# Motherboard.net
KiCad netlist of a schematic drawn in EAGLE
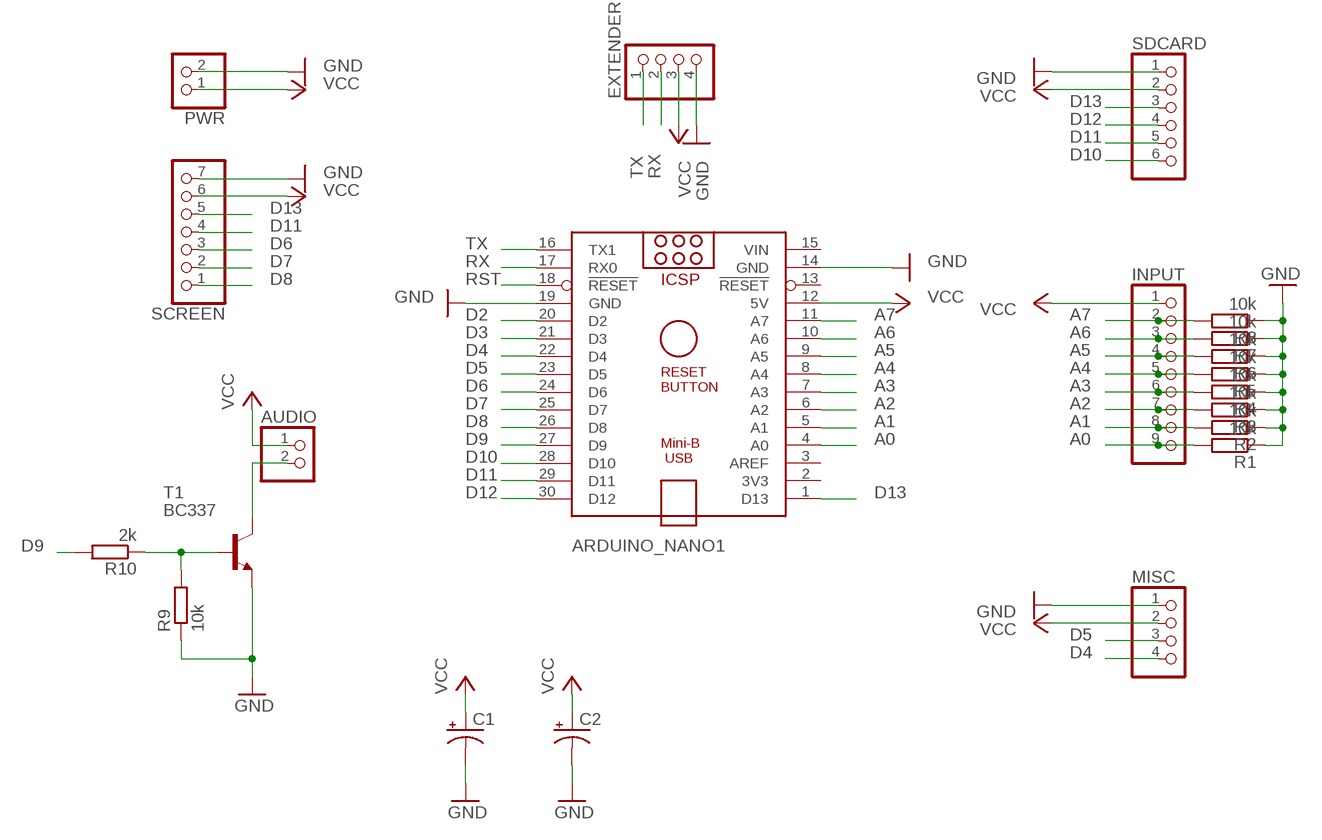
[diagram p0: schematic, sheet 1]

(export (version "E")
  (design (tool "Eeschema 10.0.6"))
  (components
    (comp (ref "ARDUINO_NANO1")
      (value "ARDUINO_NANO")
      (footprint "eagle-import:ARDUINO_NANO")
      (libsource (lib "eagle-import") (part "ARDUINO_NANO"))
    )
    (comp (ref "AUDIO")
      (value "PINHD-1X2")
      (footprint "eagle-import:1X02")
      (libsource (lib "eagle-import") (part "PINHD-1X2"))
    )
    (comp (ref "C1")
      (value "CPOL-USE2.5-6")
      (footprint "eagle-import:E2,5-6")
      (libsource (lib "eagle-import") (part "CPOL-USE2.5-6"))
    )
    (comp (ref "C2")
      (value "CPOL-USE2.5-6")
      (footprint "eagle-import:E2,5-6")
      (libsource (lib "eagle-import") (part "CPOL-USE2.5-6"))
    )
    (comp (ref "EXTENDER")
      (value "PINHD-1X4")
      (footprint "eagle-import:1X04")
      (libsource (lib "eagle-import") (part "PINHD-1X4"))
    )
    (comp (ref "INPUT")
      (value "PINHD-1X9")
      (footprint "eagle-import:1X09")
      (libsource (lib "eagle-import") (part "PINHD-1X9"))
    )
    (comp (ref "MISC")
      (value "PINHD-1X4")
      (footprint "eagle-import:1X04")
      (libsource (lib "eagle-import") (part "PINHD-1X4"))
    )
    (comp (ref "PWR")
      (value "PINHD-1X2")
      (footprint "eagle-import:1X02")
      (libsource (lib "eagle-import") (part "PINHD-1X2"))
    )
    (comp (ref "R1")
      (value "10k")
      (footprint "eagle-import:0204_7")
      (libsource (lib "eagle-import") (part "R-EU_0204/7"))
    )
    (comp (ref "R2")
      (value "10k")
      (footprint "eagle-import:0204_7")
      (libsource (lib "eagle-import") (part "R-EU_0204/7"))
    )
    (comp (ref "R3")
      (value "10k")
      (footprint "eagle-import:0204_7")
      (libsource (lib "eagle-import") (part "R-EU_0204/7"))
    )
    (comp (ref "R4")
      (value "10k")
      (footprint "eagle-import:0204_7")
      (libsource (lib "eagle-import") (part "R-EU_0204/7"))
    )
    (comp (ref "R5")
      (value "10k")
      (footprint "eagle-import:0204_7")
      (libsource (lib "eagle-import") (part "R-EU_0204/7"))
    )
    (comp (ref "R6")
      (value "10k")
      (footprint "eagle-import:0204_7")
      (libsource (lib "eagle-import") (part "R-EU_0204/7"))
    )
    (comp (ref "R7")
      (value "10k")
      (footprint "eagle-import:0204_7")
      (libsource (lib "eagle-import") (part "R-EU_0204/7"))
    )
    (comp (ref "R8")
      (value "10k")
      (footprint "eagle-import:0204_7")
      (libsource (lib "eagle-import") (part "R-EU_0204/7"))
    )
    (comp (ref "R9")
      (value "10k")
      (footprint "eagle-import:0204_7")
      (libsource (lib "eagle-import") (part "R-EU_0204/7"))
    )
    (comp (ref "R10")
      (value "2k")
      (footprint "eagle-import:0204_7")
      (libsource (lib "eagle-import") (part "R-EU_0204/7"))
    )
    (comp (ref "SCREEN")
      (value "PINHD-1X7")
      (footprint "eagle-import:1X07")
      (libsource (lib "eagle-import") (part "PINHD-1X7"))
    )
    (comp (ref "SDCARD")
      (value "PINHD-1X6")
      (footprint "eagle-import:1X06")
      (libsource (lib "eagle-import") (part "PINHD-1X6"))
    )
    (comp (ref "T1")
      (value "BC337")
      (footprint "eagle-import:TO92")
      (libsource (lib "eagle-import") (part "BC337"))
    )
  )
  (nets
    (net (code "1") (name "/A0") (class "Default")
      (node (ref "ARDUINO_NANO1") (pin "4") (pinfunction "A0_4") (pintype "bidirectional"))
      (node (ref "INPUT") (pin "9") (pinfunction "9_9") (pintype "passive"))
      (node (ref "R1") (pin "2") (pinfunction "2_2") (pintype "passive"))
    )
    (net (code "2") (name "/A1") (class "Default")
      (node (ref "ARDUINO_NANO1") (pin "5") (pinfunction "A1_5") (pintype "bidirectional"))
      (node (ref "INPUT") (pin "8") (pinfunction "8_8") (pintype "passive"))
      (node (ref "R2") (pin "2") (pinfunction "2_2") (pintype "passive"))
    )
    (net (code "3") (name "/A2") (class "Default")
      (node (ref "ARDUINO_NANO1") (pin "6") (pinfunction "A2_6") (pintype "bidirectional"))
      (node (ref "INPUT") (pin "7") (pinfunction "7_7") (pintype "passive"))
      (node (ref "R3") (pin "2") (pinfunction "2_2") (pintype "passive"))
    )
    (net (code "4") (name "/A3") (class "Default")
      (node (ref "ARDUINO_NANO1") (pin "7") (pinfunction "A3_7") (pintype "bidirectional"))
      (node (ref "INPUT") (pin "6") (pinfunction "6_6") (pintype "passive"))
      (node (ref "R4") (pin "2") (pinfunction "2_2") (pintype "passive"))
    )
    (net (code "5") (name "/A4") (class "Default")
      (node (ref "ARDUINO_NANO1") (pin "8") (pinfunction "A4_8") (pintype "bidirectional"))
      (node (ref "INPUT") (pin "5") (pinfunction "5_5") (pintype "passive"))
      (node (ref "R5") (pin "2") (pinfunction "2_2") (pintype "passive"))
    )
    (net (code "6") (name "/A5") (class "Default")
      (node (ref "ARDUINO_NANO1") (pin "9") (pinfunction "A5_9") (pintype "bidirectional"))
      (node (ref "INPUT") (pin "4") (pinfunction "4_4") (pintype "passive"))
      (node (ref "R6") (pin "2") (pinfunction "2_2") (pintype "passive"))
    )
    (net (code "7") (name "/A6") (class "Default")
      (node (ref "ARDUINO_NANO1") (pin "10") (pinfunction "A6_10") (pintype "bidirectional"))
      (node (ref "INPUT") (pin "3") (pinfunction "3_3") (pintype "passive"))
      (node (ref "R7") (pin "2") (pinfunction "2_2") (pintype "passive"))
    )
    (net (code "8") (name "/A7") (class "Default")
      (node (ref "ARDUINO_NANO1") (pin "11") (pinfunction "A7_11") (pintype "bidirectional"))
      (node (ref "INPUT") (pin "2") (pinfunction "2_2") (pintype "passive"))
      (node (ref "R8") (pin "2") (pinfunction "2_2") (pintype "passive"))
    )
    (net (code "9") (name "/D2") (class "Default")
      (node (ref "ARDUINO_NANO1") (pin "20") (pinfunction "D2_20") (pintype "bidirectional"))
    )
    (net (code "10") (name "/D3") (class "Default")
      (node (ref "ARDUINO_NANO1") (pin "21") (pinfunction "D3_21") (pintype "bidirectional"))
    )
    (net (code "11") (name "/D4") (class "Default")
      (node (ref "ARDUINO_NANO1") (pin "22") (pinfunction "D4_22") (pintype "bidirectional"))
      (node (ref "MISC") (pin "4") (pinfunction "4_4") (pintype "passive"))
    )
    (net (code "12") (name "/D5") (class "Default")
      (node (ref "ARDUINO_NANO1") (pin "23") (pinfunction "D5_23") (pintype "bidirectional"))
      (node (ref "MISC") (pin "3") (pinfunction "3_3") (pintype "passive"))
    )
    (net (code "13") (name "/D6") (class "Default")
      (node (ref "ARDUINO_NANO1") (pin "24") (pinfunction "D6_24") (pintype "bidirectional"))
      (node (ref "SCREEN") (pin "3") (pinfunction "3_3") (pintype "passive"))
    )
    (net (code "14") (name "/D7") (class "Default")
      (node (ref "ARDUINO_NANO1") (pin "25") (pinfunction "D7_25") (pintype "bidirectional"))
      (node (ref "SCREEN") (pin "2") (pinfunction "2_2") (pintype "passive"))
    )
    (net (code "15") (name "/D8") (class "Default")
      (node (ref "ARDUINO_NANO1") (pin "26") (pinfunction "D8_26") (pintype "bidirectional"))
      (node (ref "SCREEN") (pin "1") (pinfunction "1_1") (pintype "passive"))
    )
    (net (code "16") (name "/D9") (class "Default")
      (node (ref "ARDUINO_NANO1") (pin "27") (pinfunction "D9_27") (pintype "bidirectional"))
      (node (ref "R10") (pin "2") (pinfunction "2_2") (pintype "passive"))
    )
    (net (code "17") (name "/D10") (class "Default")
      (node (ref "ARDUINO_NANO1") (pin "28") (pinfunction "D10_28") (pintype "bidirectional"))
      (node (ref "SDCARD") (pin "6") (pinfunction "6_6") (pintype "passive"))
    )
    (net (code "18") (name "/D11") (class "Default")
      (node (ref "ARDUINO_NANO1") (pin "29") (pinfunction "D11_29") (pintype "bidirectional"))
      (node (ref "SCREEN") (pin "4") (pinfunction "4_4") (pintype "passive"))
      (node (ref "SDCARD") (pin "5") (pinfunction "5_5") (pintype "passive"))
    )
    (net (code "19") (name "/D12") (class "Default")
      (node (ref "ARDUINO_NANO1") (pin "30") (pinfunction "D12_30") (pintype "bidirectional"))
      (node (ref "SDCARD") (pin "4") (pinfunction "4_4") (pintype "passive"))
    )
    (net (code "20") (name "/D13") (class "Default")
      (node (ref "ARDUINO_NANO1") (pin "1") (pinfunction "D13_1") (pintype "bidirectional"))
      (node (ref "SCREEN") (pin "5") (pinfunction "5_5") (pintype "passive"))
      (node (ref "SDCARD") (pin "3") (pinfunction "3_3") (pintype "passive"))
    )
    (net (code "21") (name "/RST") (class "Default")
      (node (ref "ARDUINO_NANO1") (pin "18") (pinfunction "~{RESET}_18") (pintype "input"))
    )
    (net (code "22") (name "/RX") (class "Default")
      (node (ref "ARDUINO_NANO1") (pin "17") (pinfunction "RX0_17") (pintype "bidirectional"))
      (node (ref "EXTENDER") (pin "2") (pinfunction "2_2") (pintype "passive"))
    )
    (net (code "23") (name "/TX") (class "Default")
      (node (ref "ARDUINO_NANO1") (pin "16") (pinfunction "TX1_16") (pintype "bidirectional"))
      (node (ref "EXTENDER") (pin "1") (pinfunction "1_1") (pintype "passive"))
    )
    (net (code "24") (name "/VIN") (class "Default")
      (node (ref "ARDUINO_NANO1") (pin "15") (pinfunction "VIN_15") (pintype "power_in"))
    )
    (net (code "25") (name "GND") (class "Default")
      (node (ref "ARDUINO_NANO1") (pin "14") (pinfunction "GND_14") (pintype "power_in"))
      (node (ref "ARDUINO_NANO1") (pin "19") (pinfunction "GND_19") (pintype "power_in"))
      (node (ref "C1") (pin "-") (pinfunction "-_-") (pintype "passive"))
      (node (ref "C2") (pin "-") (pinfunction "-_-") (pintype "passive"))
      (node (ref "EXTENDER") (pin "4") (pinfunction "4_4") (pintype "passive"))
      (node (ref "MISC") (pin "1") (pinfunction "1_1") (pintype "passive"))
      (node (ref "PWR") (pin "2") (pinfunction "2_2") (pintype "passive"))
      (node (ref "R1") (pin "1") (pinfunction "1_1") (pintype "passive"))
      (node (ref "R2") (pin "1") (pinfunction "1_1") (pintype "passive"))
      (node (ref "R3") (pin "1") (pinfunction "1_1") (pintype "passive"))
      (node (ref "R4") (pin "1") (pinfunction "1_1") (pintype "passive"))
      (node (ref "R5") (pin "1") (pinfunction "1_1") (pintype "passive"))
      (node (ref "R6") (pin "1") (pinfunction "1_1") (pintype "passive"))
      (node (ref "R7") (pin "1") (pinfunction "1_1") (pintype "passive"))
      (node (ref "R8") (pin "1") (pinfunction "1_1") (pintype "passive"))
      (node (ref "R9") (pin "1") (pinfunction "1_1") (pintype "passive"))
      (node (ref "SCREEN") (pin "7") (pinfunction "7_7") (pintype "passive"))
      (node (ref "SDCARD") (pin "1") (pinfunction "1_1") (pintype "passive"))
      (node (ref "T1") (pin "1") (pinfunction "E_1") (pintype "passive"))
    )
    (net (code "26") (name "Net-(T1-B)") (class "Default")
      (node (ref "R10") (pin "1") (pinfunction "1_1") (pintype "passive"))
      (node (ref "R9") (pin "2") (pinfunction "2_2") (pintype "passive"))
      (node (ref "T1") (pin "2") (pinfunction "B_2") (pintype "passive"))
    )
    (net (code "27") (name "Net-(T1-C)") (class "Default")
      (node (ref "AUDIO") (pin "2") (pinfunction "2_2") (pintype "passive"))
      (node (ref "T1") (pin "3") (pinfunction "C_3") (pintype "passive"))
    )
    (net (code "28") (name "VCC") (class "Default")
      (node (ref "ARDUINO_NANO1") (pin "12") (pinfunction "5V_12") (pintype "power_in"))
      (node (ref "AUDIO") (pin "1") (pinfunction "1_1") (pintype "passive"))
      (node (ref "C1") (pin "+") (pinfunction "+_+") (pintype "passive"))
      (node (ref "C2") (pin "+") (pinfunction "+_+") (pintype "passive"))
      (node (ref "EXTENDER") (pin "3") (pinfunction "3_3") (pintype "passive"))
      (node (ref "INPUT") (pin "1") (pinfunction "1_1") (pintype "passive"))
      (node (ref "MISC") (pin "2") (pinfunction "2_2") (pintype "passive"))
      (node (ref "PWR") (pin "1") (pinfunction "1_1") (pintype "passive"))
      (node (ref "SCREEN") (pin "6") (pinfunction "6_6") (pintype "passive"))
      (node (ref "SDCARD") (pin "2") (pinfunction "2_2") (pintype "passive"))
    )
    (net (code "29") (name "unconnected-(ARDUINO_NANO1-3V3-Pad2)") (class "Default")
      (node (ref "ARDUINO_NANO1") (pin "2") (pinfunction "3V3_2") (pintype "output"))
    )
    (net (code "30") (name "unconnected-(ARDUINO_NANO1-AREF-Pad3)") (class "Default")
      (node (ref "ARDUINO_NANO1") (pin "3") (pinfunction "AREF_3") (pintype "input"))
    )
    (net (code "31") (name "unconnected-(ARDUINO_NANO1-~{RESET}-Pad13)") (class "Default")
      (node (ref "ARDUINO_NANO1") (pin "13") (pinfunction "~{RESET}_13") (pintype "input"))
    )
  )
)
